# modul_zegara.net
KiCad netlist of a schematic drawn in EAGLE
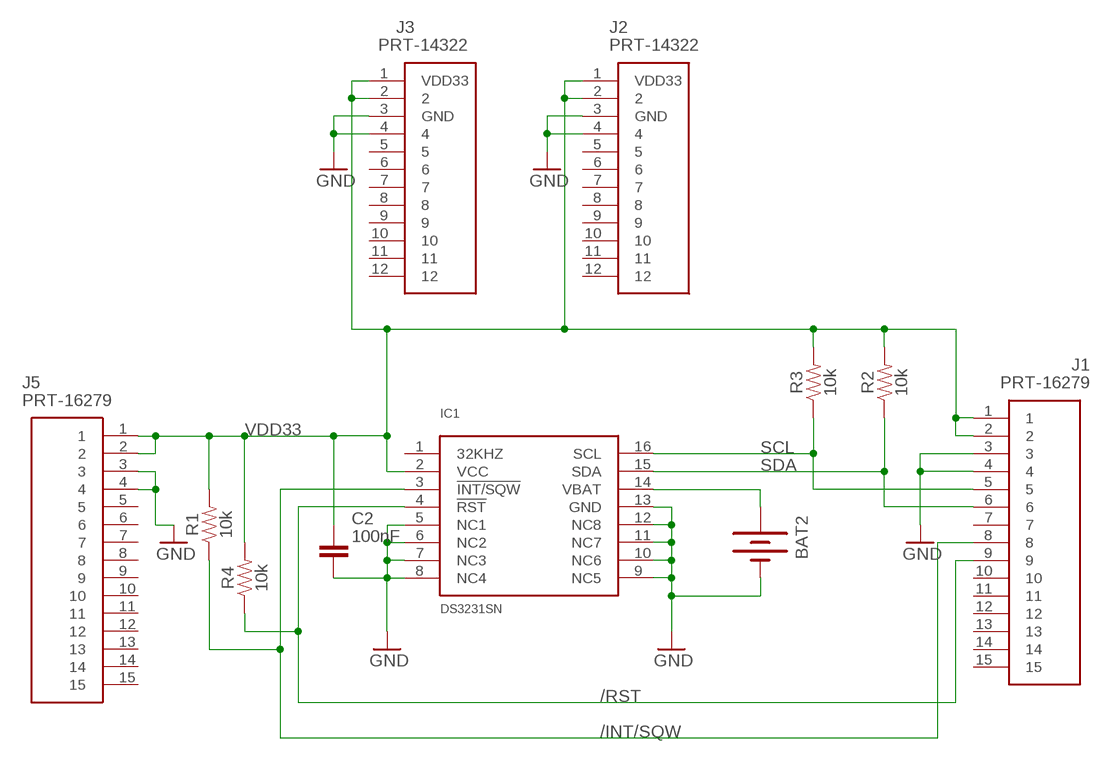
[diagram p0: schematic, sheet 1]

(export (version "E")
  (design (tool "Eeschema 10.0.6"))
  (components
    (comp (ref "BAT2")
      (value "BATTERY20PTH")
      (footprint "eagle-import:BATTCOM_20MM_PTH")
      (libsource (lib "eagle-import") (part "BATTERY20PTH"))
    )
    (comp (ref "C2")
      (value "100nF")
      (footprint "eagle-import:CAPC3216X135")
      (libsource (lib "eagle-import") (part "CCHIP-1206(3216-METRIC)_"))
    )
    (comp (ref "IC1")
      (value "DS3231SN")
      (footprint "eagle-import:SO16W")
      (libsource (lib "eagle-import") (part "DS3231SN"))
    )
    (comp (ref "J1")
      (value "PRT-16279")
      (footprint "eagle-import:PRT16279")
      (fields (field (name "MOUSER_PART_NUMBER") "474-PRT-16279"))
      (libsource (lib "eagle-import") (part "PRT-16279"))
    )
    (comp (ref "J2")
      (value "PRT-14322")
      (footprint "eagle-import:RHDR12W87P0X254_1X12_3103X250X")
      (fields (field (name "MOUSER_PART_NUMBER") "474-PRT-14322"))
      (libsource (lib "eagle-import") (part "PRT-14322"))
    )
    (comp (ref "J3")
      (value "PRT-14322")
      (footprint "eagle-import:RHDR12W87P0X254_1X12_3103X250X")
      (fields (field (name "MOUSER_PART_NUMBER") "474-PRT-14322"))
      (libsource (lib "eagle-import") (part "PRT-14322"))
    )
    (comp (ref "J5")
      (value "PRT-16279")
      (footprint "eagle-import:PRT16279")
      (fields (field (name "MOUSER_PART_NUMBER") "474-PRT-16279"))
      (libsource (lib "eagle-import") (part "PRT-16279"))
    )
    (comp (ref "R1")
      (value "10k")
      (footprint "eagle-import:AXIAL-0.3")
      (libsource (lib "eagle-import") (part "10KOHM-HORIZ-1/4W-1%"))
    )
    (comp (ref "R2")
      (value "10k")
      (footprint "eagle-import:AXIAL-0.3")
      (libsource (lib "eagle-import") (part "10KOHM-HORIZ-1/4W-1%"))
    )
    (comp (ref "R3")
      (value "10k")
      (footprint "eagle-import:AXIAL-0.3")
      (libsource (lib "eagle-import") (part "10KOHM-HORIZ-1/4W-1%"))
    )
    (comp (ref "R4")
      (value "10k")
      (footprint "eagle-import:AXIAL-0.3")
      (libsource (lib "eagle-import") (part "10KOHM-HORIZ-1/4W-1%"))
    )
  )
  (nets
    (net (code "1") (name "/SCL") (class "Default")
      (node (ref "IC1") (pin "16") (pinfunction "SCL_16") (pintype "bidirectional"))
      (node (ref "J1") (pin "5") (pinfunction "5_5") (pintype "bidirectional"))
      (node (ref "R3") (pin "P$1") (pinfunction "1_P$1") (pintype "passive"))
    )
    (net (code "2") (name "/SDA") (class "Default")
      (node (ref "IC1") (pin "15") (pinfunction "SDA_15") (pintype "bidirectional"))
      (node (ref "J1") (pin "6") (pinfunction "6_6") (pintype "bidirectional"))
      (node (ref "R2") (pin "P$1") (pinfunction "1_P$1") (pintype "passive"))
    )
    (net (code "3") (name "/VDD33") (class "Default")
      (node (ref "C2") (pin "1") (pinfunction "1_1") (pintype "passive"))
      (node (ref "IC1") (pin "2") (pinfunction "VCC_2") (pintype "bidirectional"))
      (node (ref "J1") (pin "1") (pinfunction "1_1") (pintype "bidirectional"))
      (node (ref "J1") (pin "2") (pinfunction "2_2") (pintype "bidirectional"))
      (node (ref "J2") (pin "1") (pinfunction "VDD33_1") (pintype "bidirectional"))
      (node (ref "J2") (pin "2") (pinfunction "2_2") (pintype "bidirectional"))
      (node (ref "J3") (pin "1") (pinfunction "VDD33_1") (pintype "bidirectional"))
      (node (ref "J3") (pin "2") (pinfunction "2_2") (pintype "bidirectional"))
      (node (ref "J5") (pin "1") (pinfunction "1_1") (pintype "bidirectional"))
      (node (ref "J5") (pin "2") (pinfunction "2_2") (pintype "bidirectional"))
      (node (ref "R1") (pin "P$2") (pinfunction "2_P$2") (pintype "passive"))
      (node (ref "R2") (pin "P$2") (pinfunction "2_P$2") (pintype "passive"))
      (node (ref "R3") (pin "P$2") (pinfunction "2_P$2") (pintype "passive"))
      (node (ref "R4") (pin "P$2") (pinfunction "2_P$2") (pintype "passive"))
    )
    (net (code "4") (name "/{slash}INT{slash}SQW") (class "Default")
      (node (ref "IC1") (pin "3") (pinfunction "~{INT/SQW}_3") (pintype "bidirectional"))
      (node (ref "J1") (pin "8") (pinfunction "8_8") (pintype "bidirectional"))
      (node (ref "R1") (pin "P$1") (pinfunction "1_P$1") (pintype "passive"))
    )
    (net (code "5") (name "/{slash}RST") (class "Default")
      (node (ref "IC1") (pin "4") (pinfunction "~{RST}_4") (pintype "bidirectional"))
      (node (ref "J1") (pin "9") (pinfunction "9_9") (pintype "bidirectional"))
      (node (ref "R4") (pin "P$1") (pinfunction "1_P$1") (pintype "passive"))
    )
    (net (code "6") (name "GND") (class "Default")
      (node (ref "BAT2") (pin "2") (pinfunction "-_2") (pintype "power_in"))
      (node (ref "C2") (pin "2") (pinfunction "2_2") (pintype "passive"))
      (node (ref "IC1") (pin "10") (pinfunction "NC6_10") (pintype "bidirectional"))
      (node (ref "IC1") (pin "11") (pinfunction "NC7_11") (pintype "bidirectional"))
      (node (ref "IC1") (pin "12") (pinfunction "NC8_12") (pintype "bidirectional"))
      (node (ref "IC1") (pin "13") (pinfunction "GND_13") (pintype "bidirectional"))
      (node (ref "IC1") (pin "5") (pinfunction "NC1_5") (pintype "bidirectional"))
      (node (ref "IC1") (pin "6") (pinfunction "NC2_6") (pintype "bidirectional"))
      (node (ref "IC1") (pin "7") (pinfunction "NC3_7") (pintype "bidirectional"))
      (node (ref "IC1") (pin "8") (pinfunction "NC4_8") (pintype "bidirectional"))
      (node (ref "IC1") (pin "9") (pinfunction "NC5_9") (pintype "bidirectional"))
      (node (ref "J1") (pin "3") (pinfunction "3_3") (pintype "bidirectional"))
      (node (ref "J1") (pin "4") (pinfunction "4_4") (pintype "bidirectional"))
      (node (ref "J2") (pin "3") (pinfunction "GND_3") (pintype "bidirectional"))
      (node (ref "J2") (pin "4") (pinfunction "4_4") (pintype "bidirectional"))
      (node (ref "J3") (pin "3") (pinfunction "GND_3") (pintype "bidirectional"))
      (node (ref "J3") (pin "4") (pinfunction "4_4") (pintype "bidirectional"))
      (node (ref "J5") (pin "3") (pinfunction "3_3") (pintype "bidirectional"))
      (node (ref "J5") (pin "4") (pinfunction "4_4") (pintype "bidirectional"))
    )
    (net (code "7") (name "Net-(BAT2-+)") (class "Default")
      (node (ref "BAT2") (pin "1") (pinfunction "+_1") (pintype "power_in"))
      (node (ref "IC1") (pin "14") (pinfunction "VBAT_14") (pintype "bidirectional"))
    )
    (net (code "8") (name "unconnected-(IC1-32KHZ-Pad1)") (class "Default")
      (node (ref "IC1") (pin "1") (pinfunction "32KHZ_1") (pintype "bidirectional"))
    )
    (net (code "9") (name "unconnected-(J1-Pad7)") (class "Default")
      (node (ref "J1") (pin "7") (pinfunction "7_7") (pintype "bidirectional"))
    )
    (net (code "10") (name "unconnected-(J1-Pad10)") (class "Default")
      (node (ref "J1") (pin "10") (pinfunction "10_10") (pintype "bidirectional"))
    )
    (net (code "11") (name "unconnected-(J1-Pad11)") (class "Default")
      (node (ref "J1") (pin "11") (pinfunction "11_11") (pintype "bidirectional"))
    )
    (net (code "12") (name "unconnected-(J1-Pad12)") (class "Default")
      (node (ref "J1") (pin "12") (pinfunction "12_12") (pintype "bidirectional"))
    )
    (net (code "13") (name "unconnected-(J1-Pad13)") (class "Default")
      (node (ref "J1") (pin "13") (pinfunction "13_13") (pintype "bidirectional"))
    )
    (net (code "14") (name "unconnected-(J1-Pad14)") (class "Default")
      (node (ref "J1") (pin "14") (pinfunction "14_14") (pintype "bidirectional"))
    )
    (net (code "15") (name "unconnected-(J1-Pad15)") (class "Default")
      (node (ref "J1") (pin "15") (pinfunction "15_15") (pintype "bidirectional"))
    )
    (net (code "16") (name "unconnected-(J2-Pad5)") (class "Default")
      (node (ref "J2") (pin "5") (pinfunction "5_5") (pintype "bidirectional"))
    )
    (net (code "17") (name "unconnected-(J2-Pad6)") (class "Default")
      (node (ref "J2") (pin "6") (pinfunction "6_6") (pintype "bidirectional"))
    )
    (net (code "18") (name "unconnected-(J2-Pad7)") (class "Default")
      (node (ref "J2") (pin "7") (pinfunction "7_7") (pintype "bidirectional"))
    )
    (net (code "19") (name "unconnected-(J2-Pad8)") (class "Default")
      (node (ref "J2") (pin "8") (pinfunction "8_8") (pintype "bidirectional"))
    )
    (net (code "20") (name "unconnected-(J2-Pad9)") (class "Default")
      (node (ref "J2") (pin "9") (pinfunction "9_9") (pintype "bidirectional"))
    )
    (net (code "21") (name "unconnected-(J2-Pad10)") (class "Default")
      (node (ref "J2") (pin "10") (pinfunction "10_10") (pintype "bidirectional"))
    )
    (net (code "22") (name "unconnected-(J2-Pad11)") (class "Default")
      (node (ref "J2") (pin "11") (pinfunction "11_11") (pintype "bidirectional"))
    )
    (net (code "23") (name "unconnected-(J2-Pad12)") (class "Default")
      (node (ref "J2") (pin "12") (pinfunction "12_12") (pintype "bidirectional"))
    )
    (net (code "24") (name "unconnected-(J3-Pad5)") (class "Default")
      (node (ref "J3") (pin "5") (pinfunction "5_5") (pintype "bidirectional"))
    )
    (net (code "25") (name "unconnected-(J3-Pad6)") (class "Default")
      (node (ref "J3") (pin "6") (pinfunction "6_6") (pintype "bidirectional"))
    )
    (net (code "26") (name "unconnected-(J3-Pad7)") (class "Default")
      (node (ref "J3") (pin "7") (pinfunction "7_7") (pintype "bidirectional"))
    )
    (net (code "27") (name "unconnected-(J3-Pad8)") (class "Default")
      (node (ref "J3") (pin "8") (pinfunction "8_8") (pintype "bidirectional"))
    )
    (net (code "28") (name "unconnected-(J3-Pad9)") (class "Default")
      (node (ref "J3") (pin "9") (pinfunction "9_9") (pintype "bidirectional"))
    )
    (net (code "29") (name "unconnected-(J3-Pad10)") (class "Default")
      (node (ref "J3") (pin "10") (pinfunction "10_10") (pintype "bidirectional"))
    )
    (net (code "30") (name "unconnected-(J3-Pad11)") (class "Default")
      (node (ref "J3") (pin "11") (pinfunction "11_11") (pintype "bidirectional"))
    )
    (net (code "31") (name "unconnected-(J3-Pad12)") (class "Default")
      (node (ref "J3") (pin "12") (pinfunction "12_12") (pintype "bidirectional"))
    )
    (net (code "32") (name "unconnected-(J5-Pad5)") (class "Default")
      (node (ref "J5") (pin "5") (pinfunction "5_5") (pintype "bidirectional"))
    )
    (net (code "33") (name "unconnected-(J5-Pad6)") (class "Default")
      (node (ref "J5") (pin "6") (pinfunction "6_6") (pintype "bidirectional"))
    )
    (net (code "34") (name "unconnected-(J5-Pad7)") (class "Default")
      (node (ref "J5") (pin "7") (pinfunction "7_7") (pintype "bidirectional"))
    )
    (net (code "35") (name "unconnected-(J5-Pad8)") (class "Default")
      (node (ref "J5") (pin "8") (pinfunction "8_8") (pintype "bidirectional"))
    )
    (net (code "36") (name "unconnected-(J5-Pad9)") (class "Default")
      (node (ref "J5") (pin "9") (pinfunction "9_9") (pintype "bidirectional"))
    )
    (net (code "37") (name "unconnected-(J5-Pad10)") (class "Default")
      (node (ref "J5") (pin "10") (pinfunction "10_10") (pintype "bidirectional"))
    )
    (net (code "38") (name "unconnected-(J5-Pad11)") (class "Default")
      (node (ref "J5") (pin "11") (pinfunction "11_11") (pintype "bidirectional"))
    )
    (net (code "39") (name "unconnected-(J5-Pad12)") (class "Default")
      (node (ref "J5") (pin "12") (pinfunction "12_12") (pintype "bidirectional"))
    )
    (net (code "40") (name "unconnected-(J5-Pad13)") (class "Default")
      (node (ref "J5") (pin "13") (pinfunction "13_13") (pintype "bidirectional"))
    )
    (net (code "41") (name "unconnected-(J5-Pad14)") (class "Default")
      (node (ref "J5") (pin "14") (pinfunction "14_14") (pintype "bidirectional"))
    )
    (net (code "42") (name "unconnected-(J5-Pad15)") (class "Default")
      (node (ref "J5") (pin "15") (pinfunction "15_15") (pintype "bidirectional"))
    )
  )
)
